# eigenes_OVMS.net
KiCad netlist of a schematic drawn in EAGLE
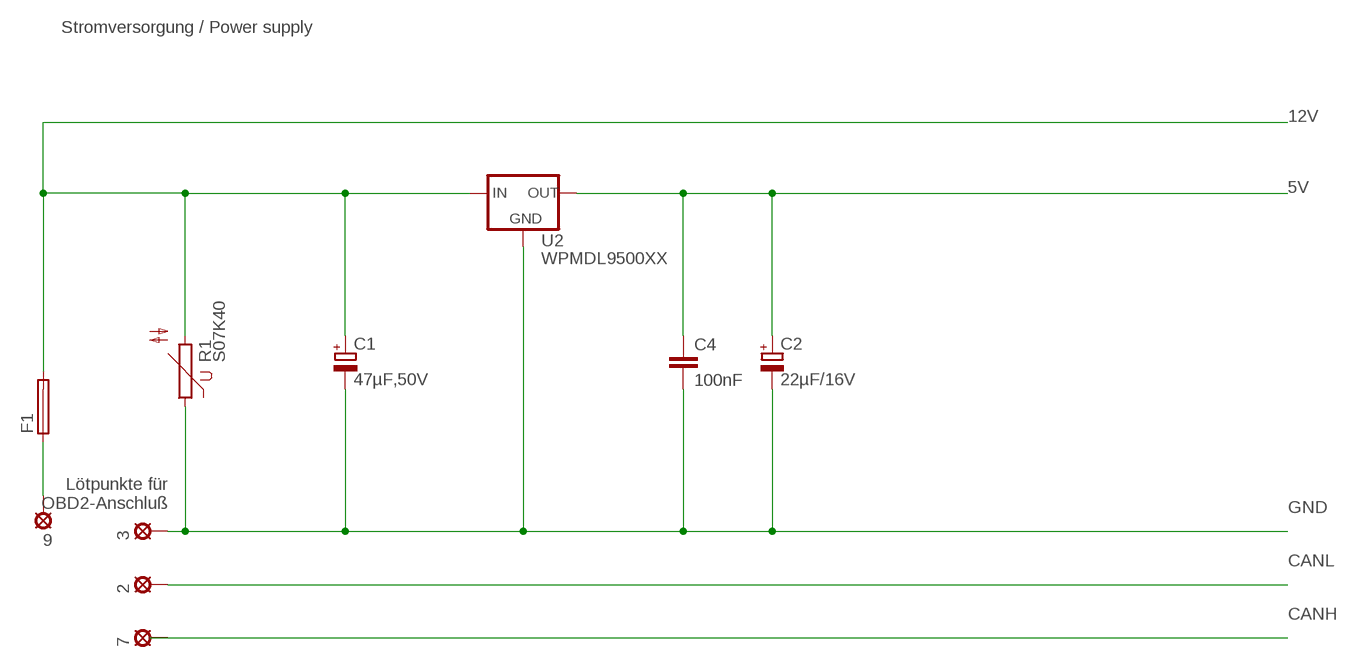
[diagram p0: schematic, sheet 1]
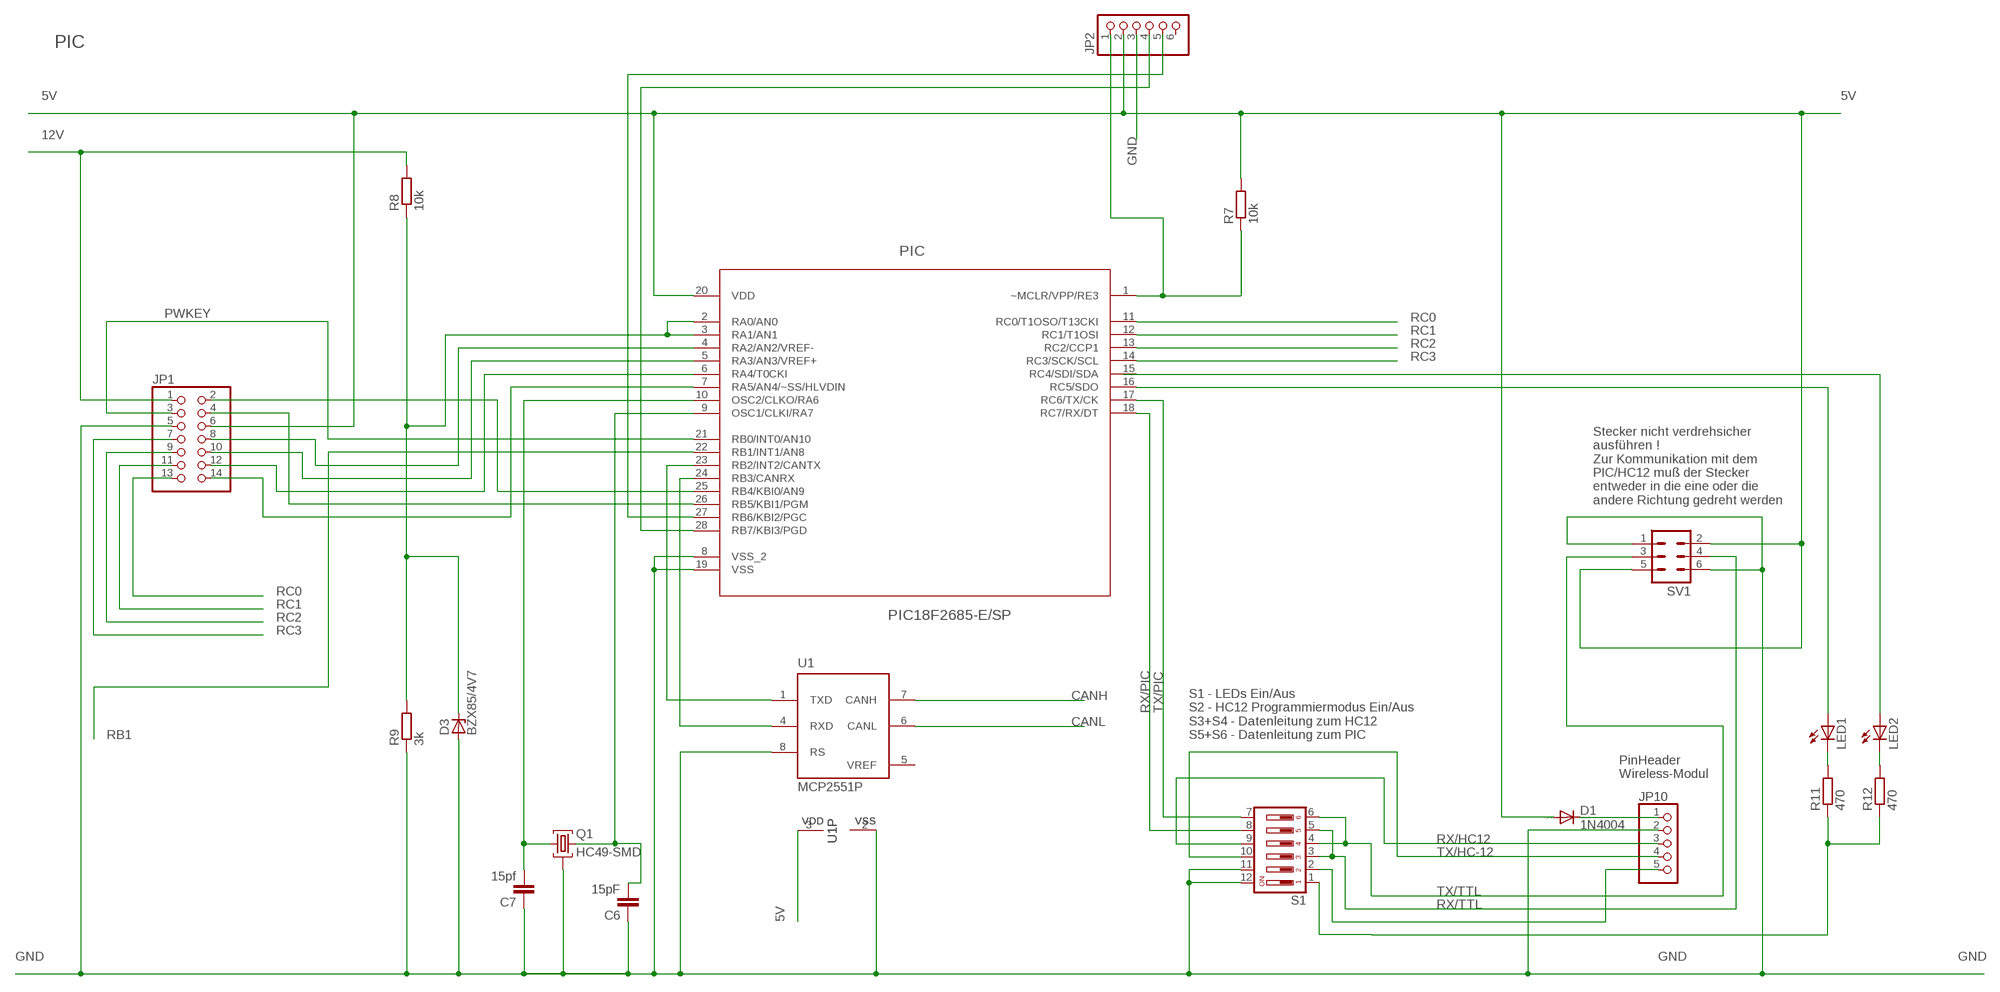
[diagram p1: schematic, sheet 2]
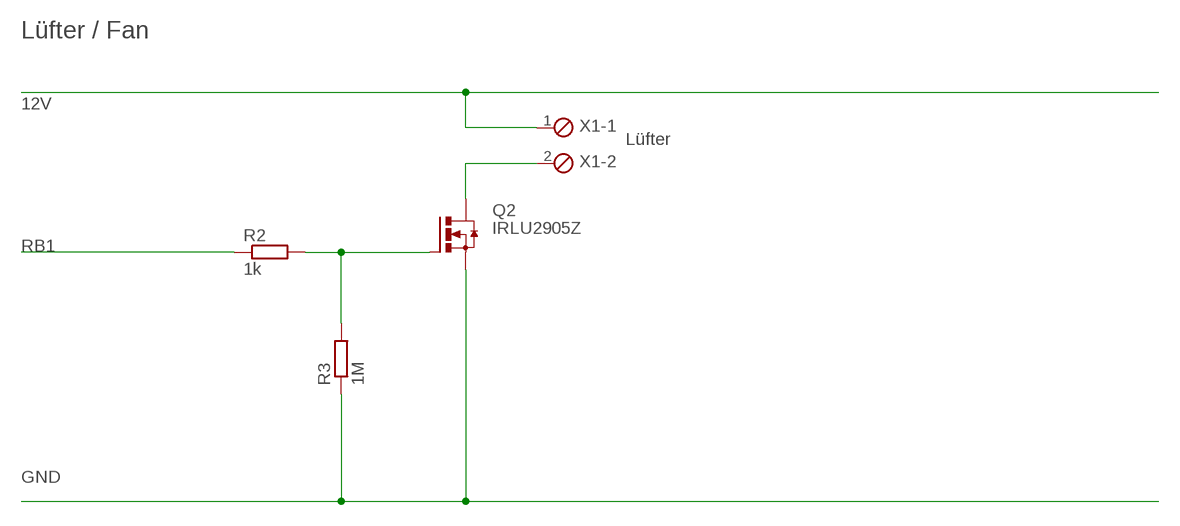
[diagram p2: schematic, sheet 3]

(export (version "E")
  (design (tool "Eeschema 10.0.6"))
  (components
    (comp (ref "C6")
      (value "15pF")
      (footprint "eagle-import:C025-025X050")
      (libsource (lib "eagle-import") (part "C-EU025-025X050"))
    )
    (comp (ref "C7")
      (value "15pf")
      (footprint "eagle-import:C025-025X050")
      (libsource (lib "eagle-import") (part "C-EU025-025X050"))
    )
    (comp (ref "D1")
      (value "1N4004")
      (footprint "eagle-import:DO41-10")
      (libsource (lib "eagle-import") (part "1N4004"))
    )
    (comp (ref "D3")
      (value "BZX85/4V7")
      (footprint "eagle-import:DO41Z10")
      (libsource (lib "eagle-import") (part "BZX85"))
    )
    (comp (ref "JP1")
      (value "PINHD-2X7")
      (footprint "eagle-import:2X07")
      (libsource (lib "eagle-import") (part "PINHD-2X7"))
    )
    (comp (ref "JP2")
      (value "PINHD-1X6")
      (footprint "eagle-import:1X06")
      (libsource (lib "eagle-import") (part "PINHD-1X6"))
    )
    (comp (ref "JP10")
      (value "PINHD-1X5")
      (footprint "eagle-import:1X05")
      (libsource (lib "eagle-import") (part "PINHD-1X5"))
    )
    (comp (ref "LED1")
      (value "LED3MM")
      (footprint "eagle-import:LED3MM")
      (libsource (lib "eagle-import") (part "LED3MM"))
    )
    (comp (ref "LED2")
      (value "LED3MM")
      (footprint "eagle-import:LED3MM")
      (libsource (lib "eagle-import") (part "LED3MM"))
    )
    (comp (ref "PIC")
      (value "PIC18F2685-E/SP")
      (footprint "eagle-import:DIP254P762X508-28")
      (libsource (lib "eagle-import") (part "PIC18F2685-E/SP"))
    )
    (comp (ref "Q1")
      (value "HC49-SMD")
      (footprint "eagle-import:HC49U")
      (libsource (lib "eagle-import") (part "12M10BHC49T"))
    )
    (comp (ref "R7")
      (value "10k")
      (footprint "eagle-import:0207_7")
      (libsource (lib "eagle-import") (part "R-EU_0207/7"))
    )
    (comp (ref "R8")
      (value "10k")
      (footprint "eagle-import:0207_7")
      (libsource (lib "eagle-import") (part "R-EU_0207/7"))
    )
    (comp (ref "R9")
      (value "3k")
      (footprint "eagle-import:0207_7")
      (libsource (lib "eagle-import") (part "R-EU_0207/7"))
    )
    (comp (ref "R11")
      (value "470")
      (footprint "eagle-import:0207_7")
      (libsource (lib "eagle-import") (part "R-EU_0207/7"))
    )
    (comp (ref "R12")
      (value "470")
      (footprint "eagle-import:0207_7")
      (libsource (lib "eagle-import") (part "R-EU_0207/7"))
    )
    (comp (ref "S1")
      (value "DIP06YL")
      (footprint "eagle-import:DIP06YL")
      (libsource (lib "eagle-import") (part "DIP06YL"))
    )
    (comp (ref "SV1")
      (value "ML6L")
      (footprint "eagle-import:ML6L")
      (libsource (lib "eagle-import") (part "ML6L"))
    )
    (comp (ref "U1")
      (value "MCP2551P")
      (footprint "eagle-import:DIL8")
      (libsource (lib "eagle-import") (part "MCP2551P"))
    )
    (comp (ref "Q2")
      (value "IRLU2905Z")
      (footprint "eagle-import:TO251AA-V")
      (libsource (lib "eagle-import") (part "IRLU2905Z"))
    )
    (comp (ref "R2")
      (value "1k")
      (footprint "eagle-import:0207_7")
      (libsource (lib "eagle-import") (part "resistor_R-EU_0207/7"))
    )
    (comp (ref "R3")
      (value "1M")
      (footprint "eagle-import:0207_7")
      (libsource (lib "eagle-import") (part "resistor_R-EU_0207/7"))
    )
    (comp (ref "X1")
      (value "MPT2")
      (footprint "eagle-import:2POL254")
      (libsource (lib "eagle-import") (part "MPT2"))
    )
    (comp (ref "2")
      (value "LSP10")
      (footprint "eagle-import:LSP10")
      (libsource (lib "eagle-import") (part "LSP10"))
    )
    (comp (ref "3")
      (value "LSP10")
      (footprint "eagle-import:LSP10")
      (libsource (lib "eagle-import") (part "LSP10"))
    )
    (comp (ref "7")
      (value "LSP10")
      (footprint "eagle-import:LSP10")
      (libsource (lib "eagle-import") (part "LSP10"))
    )
    (comp (ref "9")
      (value "LSP10")
      (footprint "eagle-import:LSP10")
      (libsource (lib "eagle-import") (part "LSP10"))
    )
    (comp (ref "C1")
      (value "47µF,50V")
      (footprint "eagle-import:E2,5-7")
      (libsource (lib "eagle-import") (part "CPOL-EUE2.5-7"))
    )
    (comp (ref "C2")
      (value "22µF/16V")
      (footprint "eagle-import:E2,5-5")
      (libsource (lib "eagle-import") (part "CPOL-EUE2.5-5"))
    )
    (comp (ref "C4")
      (value "100nF")
      (footprint "eagle-import:C025-025X050")
      (libsource (lib "eagle-import") (part "C-EU025-025X050"))
    )
    (comp (ref "F1")
      (value "19559")
      (footprint "eagle-import:19559")
      (fields (field (name "MPN") "55900000001"))
      (libsource (lib "eagle-import") (part "19559"))
    )
    (comp (ref "R1")
      (value "S07K40")
      (footprint "eagle-import:S07K40")
      (libsource (lib "eagle-import") (part "S07K40"))
    )
    (comp (ref "U2")
      (value "WPMDL9500XX")
      (footprint "eagle-import:WPMDL9500")
      (libsource (lib "eagle-import") (part "WPMDL9500XX"))
    )
  )
  (nets
    (net (code "1") (name "5V") (class "Default")
      (node (ref "C2") (pin "+") (pinfunction "+_+") (pintype "passive"))
      (node (ref "C4") (pin "1") (pinfunction "1_1") (pintype "passive"))
      (node (ref "D1") (pin "A") (pinfunction "A_A") (pintype "passive"))
      (node (ref "JP1") (pin "6") (pinfunction "6_6") (pintype "passive"))
      (node (ref "JP2") (pin "2") (pinfunction "2_2") (pintype "passive"))
      (node (ref "PIC") (pin "20") (pinfunction "VDD_20") (pintype "power_in"))
      (node (ref "R7") (pin "2") (pinfunction "2_2") (pintype "passive"))
      (node (ref "SV1") (pin "2") (pinfunction "2_2") (pintype "passive"))
      (node (ref "SV1") (pin "5") (pinfunction "5_5") (pintype "passive"))
      (node (ref "U1") (pin "3") (pinfunction "VDD_3") (pintype "power_in"))
      (node (ref "U2") (pin "OUT") (pinfunction "OUT_OUT") (pintype "passive"))
    )
    (net (code "2") (name "12V") (class "Default")
      (node (ref "C1") (pin "+") (pinfunction "+_+") (pintype "passive"))
      (node (ref "F1") (pin "2") (pinfunction "2_2") (pintype "passive"))
      (node (ref "JP1") (pin "1") (pinfunction "1_1") (pintype "passive"))
      (node (ref "R1") (pin "2") (pinfunction "2_2") (pintype "passive"))
      (node (ref "R8") (pin "2") (pinfunction "2_2") (pintype "passive"))
      (node (ref "U2") (pin "IN") (pinfunction "IN_IN") (pintype "input"))
      (node (ref "X1") (pin "1") (pinfunction "1_1") (pintype "passive"))
    )
    (net (code "3") (name "CANH") (class "Default")
      (node (ref "7") (pin "MP") (pinfunction "MP_MP") (pintype "passive"))
      (node (ref "U1") (pin "7") (pinfunction "CANH_7") (pintype "bidirectional"))
    )
    (net (code "4") (name "CANL") (class "Default")
      (node (ref "2") (pin "MP") (pinfunction "MP_MP") (pintype "passive"))
      (node (ref "U1") (pin "6") (pinfunction "CANL_6") (pintype "bidirectional"))
    )
    (net (code "5") (name "GND") (class "Default")
      (node (ref "3") (pin "MP") (pinfunction "MP_MP") (pintype "passive"))
      (node (ref "C1") (pin "-") (pinfunction "-_-") (pintype "passive"))
      (node (ref "C2") (pin "-") (pinfunction "-_-") (pintype "passive"))
      (node (ref "C4") (pin "2") (pinfunction "2_2") (pintype "passive"))
      (node (ref "C6") (pin "1") (pinfunction "1_1") (pintype "passive"))
      (node (ref "C7") (pin "1") (pinfunction "1_1") (pintype "passive"))
      (node (ref "D3") (pin "A") (pinfunction "A_A") (pintype "passive"))
      (node (ref "JP1") (pin "5") (pinfunction "5_5") (pintype "passive"))
      (node (ref "JP10") (pin "2") (pinfunction "2_2") (pintype "passive"))
      (node (ref "JP2") (pin "3") (pinfunction "3_3") (pintype "passive"))
      (node (ref "PIC") (pin "19") (pinfunction "VSS_19") (pintype "power_in"))
      (node (ref "PIC") (pin "8") (pinfunction "VSS_2_8") (pintype "power_in"))
      (node (ref "Q1") (pin "2") (pinfunction "2_2") (pintype "passive"))
      (node (ref "Q2") (pin "3") (pinfunction "S_3") (pintype "passive"))
      (node (ref "R1") (pin "1") (pinfunction "1_1") (pintype "passive"))
      (node (ref "R3") (pin "1") (pinfunction "1_1") (pintype "passive"))
      (node (ref "R9") (pin "1") (pinfunction "1_1") (pintype "passive"))
      (node (ref "S1") (pin "11") (pinfunction "11_11") (pintype "passive"))
      (node (ref "S1") (pin "12") (pinfunction "12_12") (pintype "passive"))
      (node (ref "SV1") (pin "1") (pinfunction "1_1") (pintype "passive"))
      (node (ref "SV1") (pin "6") (pinfunction "6_6") (pintype "passive"))
      (node (ref "U1") (pin "2") (pinfunction "VSS_2") (pintype "power_in"))
      (node (ref "U1") (pin "8") (pinfunction "RS_8") (pintype "input"))
      (node (ref "U2") (pin "GND") (pinfunction "GND_GND") (pintype "input"))
    )
    (net (code "6") (name "Net-(9-PadMP)") (class "Default")
      (node (ref "9") (pin "MP") (pinfunction "MP_MP") (pintype "passive"))
      (node (ref "F1") (pin "1") (pinfunction "1_1") (pintype "passive"))
    )
    (net (code "7") (name "Net-(D1-PadC)") (class "Default")
      (node (ref "D1") (pin "C") (pinfunction "C_C") (pintype "passive"))
      (node (ref "JP10") (pin "1") (pinfunction "1_1") (pintype "passive"))
    )
    (net (code "8") (name "Net-(JP10-Pad5)") (class "Default")
      (node (ref "JP10") (pin "5") (pinfunction "5_5") (pintype "passive"))
      (node (ref "S1") (pin "2") (pinfunction "2_2") (pintype "passive"))
    )
    (net (code "9") (name "Net-(LED1-C)") (class "Default")
      (node (ref "LED1") (pin "K") (pinfunction "C_K") (pintype "passive"))
      (node (ref "R11") (pin "2") (pinfunction "2_2") (pintype "passive"))
    )
    (net (code "10") (name "Net-(LED2-C)") (class "Default")
      (node (ref "LED2") (pin "K") (pinfunction "C_K") (pintype "passive"))
      (node (ref "R12") (pin "2") (pinfunction "2_2") (pintype "passive"))
    )
    (net (code "11") (name "Net-(PIC-OSC1{slash}CLKI{slash}RA7)") (class "Default")
      (node (ref "C6") (pin "2") (pinfunction "2_2") (pintype "passive"))
      (node (ref "PIC") (pin "9") (pinfunction "OSC1/CLKI/RA7_9") (pintype "bidirectional"))
      (node (ref "Q1") (pin "3") (pinfunction "3_3") (pintype "passive"))
    )
    (net (code "12") (name "Net-(PIC-OSC2{slash}CLKO{slash}RA6)") (class "Default")
      (node (ref "C7") (pin "2") (pinfunction "2_2") (pintype "passive"))
      (node (ref "PIC") (pin "10") (pinfunction "OSC2/CLKO/RA6_10") (pintype "bidirectional"))
      (node (ref "Q1") (pin "1") (pinfunction "1_1") (pintype "passive"))
    )
    (net (code "13") (name "Net-(PIC-RA0{slash}AN0)") (class "Default")
      (node (ref "D3") (pin "C") (pinfunction "C_C") (pintype "passive"))
      (node (ref "PIC") (pin "2") (pinfunction "RA0/AN0_2") (pintype "bidirectional"))
      (node (ref "PIC") (pin "3") (pinfunction "RA1/AN1_3") (pintype "bidirectional"))
      (node (ref "R8") (pin "1") (pinfunction "1_1") (pintype "passive"))
      (node (ref "R9") (pin "2") (pinfunction "2_2") (pintype "passive"))
    )
    (net (code "14") (name "Net-(PIC-RA2{slash}AN2{slash}VREF-)") (class "Default")
      (node (ref "JP1") (pin "8") (pinfunction "8_8") (pintype "passive"))
      (node (ref "PIC") (pin "4") (pinfunction "RA2/AN2/VREF-_4") (pintype "bidirectional"))
    )
    (net (code "15") (name "Net-(PIC-RA3{slash}AN3{slash}VREF+)") (class "Default")
      (node (ref "JP1") (pin "10") (pinfunction "10_10") (pintype "passive"))
      (node (ref "PIC") (pin "5") (pinfunction "RA3/AN3/VREF+_5") (pintype "bidirectional"))
    )
    (net (code "16") (name "Net-(PIC-RA4{slash}T0CKI)") (class "Default")
      (node (ref "JP1") (pin "12") (pinfunction "12_12") (pintype "passive"))
      (node (ref "PIC") (pin "6") (pinfunction "RA4/T0CKI_6") (pintype "bidirectional"))
    )
    (net (code "17") (name "Net-(PIC-RA5{slash}AN4{slash}~{SS{slash}HLVDIN})") (class "Default")
      (node (ref "JP1") (pin "14") (pinfunction "14_14") (pintype "passive"))
      (node (ref "PIC") (pin "7") (pinfunction "RA5/AN4/~{SS/HLVDIN}_7") (pintype "bidirectional"))
    )
    (net (code "18") (name "Net-(PIC-RB2{slash}INT2{slash}CANTX)") (class "Default")
      (node (ref "PIC") (pin "23") (pinfunction "RB2/INT2/CANTX_23") (pintype "bidirectional"))
      (node (ref "U1") (pin "1") (pinfunction "TXD_1") (pintype "input"))
    )
    (net (code "19") (name "Net-(PIC-RB3{slash}CANRX)") (class "Default")
      (node (ref "PIC") (pin "24") (pinfunction "RB3/CANRX_24") (pintype "bidirectional"))
      (node (ref "U1") (pin "4") (pinfunction "RXD_4") (pintype "output"))
    )
    (net (code "20") (name "Net-(PIC-RB4{slash}KBI0{slash}AN9)") (class "Default")
      (node (ref "JP1") (pin "2") (pinfunction "2_2") (pintype "passive"))
      (node (ref "PIC") (pin "25") (pinfunction "RB4/KBI0/AN9_25") (pintype "bidirectional"))
    )
    (net (code "21") (name "Net-(PIC-RB5{slash}KBI1{slash}PGM)") (class "Default")
      (node (ref "JP1") (pin "4") (pinfunction "4_4") (pintype "passive"))
      (node (ref "PIC") (pin "26") (pinfunction "RB5/KBI1/PGM_26") (pintype "bidirectional"))
    )
    (net (code "22") (name "Net-(PIC-RB6{slash}KBI2{slash}PGC)") (class "Default")
      (node (ref "JP2") (pin "5") (pinfunction "5_5") (pintype "passive"))
      (node (ref "PIC") (pin "27") (pinfunction "RB6/KBI2/PGC_27") (pintype "bidirectional"))
    )
    (net (code "23") (name "Net-(PIC-RB7{slash}KBI3{slash}PGD)") (class "Default")
      (node (ref "JP2") (pin "4") (pinfunction "4_4") (pintype "passive"))
      (node (ref "PIC") (pin "28") (pinfunction "RB7/KBI3/PGD_28") (pintype "bidirectional"))
    )
    (net (code "24") (name "Net-(PIC-RC4{slash}SDI{slash}SDA)") (class "Default")
      (node (ref "LED2") (pin "A") (pinfunction "A_A") (pintype "passive"))
      (node (ref "PIC") (pin "15") (pinfunction "RC4/SDI/SDA_15") (pintype "bidirectional"))
    )
    (net (code "25") (name "Net-(PIC-RC5{slash}SDO)") (class "Default")
      (node (ref "LED1") (pin "A") (pinfunction "A_A") (pintype "passive"))
      (node (ref "PIC") (pin "16") (pinfunction "RC5/SDO_16") (pintype "bidirectional"))
    )
    (net (code "26") (name "Net-(PIC-~{MCLR{slash}VPP{slash}RE3})") (class "Default")
      (node (ref "JP2") (pin "1") (pinfunction "1_1") (pintype "passive"))
      (node (ref "PIC") (pin "1") (pinfunction "~{MCLR/VPP/RE3}_1") (pintype "bidirectional"))
      (node (ref "R7") (pin "1") (pinfunction "1_1") (pintype "passive"))
    )
    (net (code "27") (name "Net-(Q2-D)") (class "Default")
      (node (ref "Q2") (pin "2") (pinfunction "D_2") (pintype "passive"))
      (node (ref "X1") (pin "2") (pinfunction "1_2") (pintype "passive"))
    )
    (net (code "28") (name "Net-(Q2-G)") (class "Default")
      (node (ref "Q2") (pin "1") (pinfunction "G_1") (pintype "passive"))
      (node (ref "R2") (pin "2") (pinfunction "2_2") (pintype "passive"))
      (node (ref "R3") (pin "2") (pinfunction "2_2") (pintype "passive"))
    )
    (net (code "29") (name "Net-(R11-Pad1)") (class "Default")
      (node (ref "R11") (pin "1") (pinfunction "1_1") (pintype "passive"))
      (node (ref "R12") (pin "1") (pinfunction "1_1") (pintype "passive"))
      (node (ref "S1") (pin "1") (pinfunction "1_1") (pintype "passive"))
    )
    (net (code "30") (name "PWKEY") (class "Default")
      (node (ref "JP1") (pin "3") (pinfunction "3_3") (pintype "passive"))
      (node (ref "PIC") (pin "21") (pinfunction "RB0/INT0/AN10_21") (pintype "bidirectional"))
    )
    (net (code "31") (name "RB1") (class "Default")
      (node (ref "PIC") (pin "22") (pinfunction "RB1/INT1/AN8_22") (pintype "bidirectional"))
      (node (ref "R2") (pin "1") (pinfunction "1_1") (pintype "passive"))
    )
    (net (code "32") (name "RC0") (class "Default")
      (node (ref "JP1") (pin "13") (pinfunction "13_13") (pintype "passive"))
      (node (ref "PIC") (pin "11") (pinfunction "RC0/T1OSO/T13CKI_11") (pintype "bidirectional"))
    )
    (net (code "33") (name "RC1") (class "Default")
      (node (ref "JP1") (pin "11") (pinfunction "11_11") (pintype "passive"))
      (node (ref "PIC") (pin "12") (pinfunction "RC1/T1OSI_12") (pintype "bidirectional"))
    )
    (net (code "34") (name "RC2") (class "Default")
      (node (ref "JP1") (pin "9") (pinfunction "9_9") (pintype "passive"))
      (node (ref "PIC") (pin "13") (pinfunction "RC2/CCP1_13") (pintype "bidirectional"))
    )
    (net (code "35") (name "RC3") (class "Default")
      (node (ref "JP1") (pin "7") (pinfunction "7_7") (pintype "passive"))
      (node (ref "PIC") (pin "14") (pinfunction "RC3/SCK/SCL_14") (pintype "bidirectional"))
    )
    (net (code "36") (name "RX{slash}HC12") (class "Default")
      (node (ref "JP10") (pin "3") (pinfunction "3_3") (pintype "passive"))
      (node (ref "S1") (pin "9") (pinfunction "9_9") (pintype "passive"))
    )
    (net (code "37") (name "RX{slash}PIC") (class "Default")
      (node (ref "PIC") (pin "18") (pinfunction "RC7/RX/DT_18") (pintype "bidirectional"))
      (node (ref "S1") (pin "8") (pinfunction "8_8") (pintype "passive"))
    )
    (net (code "38") (name "RX{slash}TTL") (class "Default")
      (node (ref "S1") (pin "3") (pinfunction "3_3") (pintype "passive"))
      (node (ref "S1") (pin "5") (pinfunction "5_5") (pintype "passive"))
      (node (ref "SV1") (pin "4") (pinfunction "4_4") (pintype "passive"))
    )
    (net (code "39") (name "TX{slash}HC-12") (class "Default")
      (node (ref "JP10") (pin "4") (pinfunction "4_4") (pintype "passive"))
      (node (ref "S1") (pin "10") (pinfunction "10_10") (pintype "passive"))
    )
    (net (code "40") (name "TX{slash}PIC") (class "Default")
      (node (ref "PIC") (pin "17") (pinfunction "RC6/TX/CK_17") (pintype "bidirectional"))
      (node (ref "S1") (pin "7") (pinfunction "7_7") (pintype "passive"))
    )
    (net (code "41") (name "TX{slash}TTL") (class "Default")
      (node (ref "S1") (pin "4") (pinfunction "4_4") (pintype "passive"))
      (node (ref "S1") (pin "6") (pinfunction "6_6") (pintype "passive"))
      (node (ref "SV1") (pin "3") (pinfunction "3_3") (pintype "passive"))
    )
    (net (code "42") (name "VREF") (class "Default")
      (node (ref "U1") (pin "5") (pinfunction "VREF_5") (pintype "power_in"))
    )
    (net (code "43") (name "unconnected-(JP2-Pad6)") (class "Default")
      (node (ref "JP2") (pin "6") (pinfunction "6_6") (pintype "passive"))
    )
  )
)
